# LED_Ring.net
KiCad netlist of a schematic drawn in Altium Designer
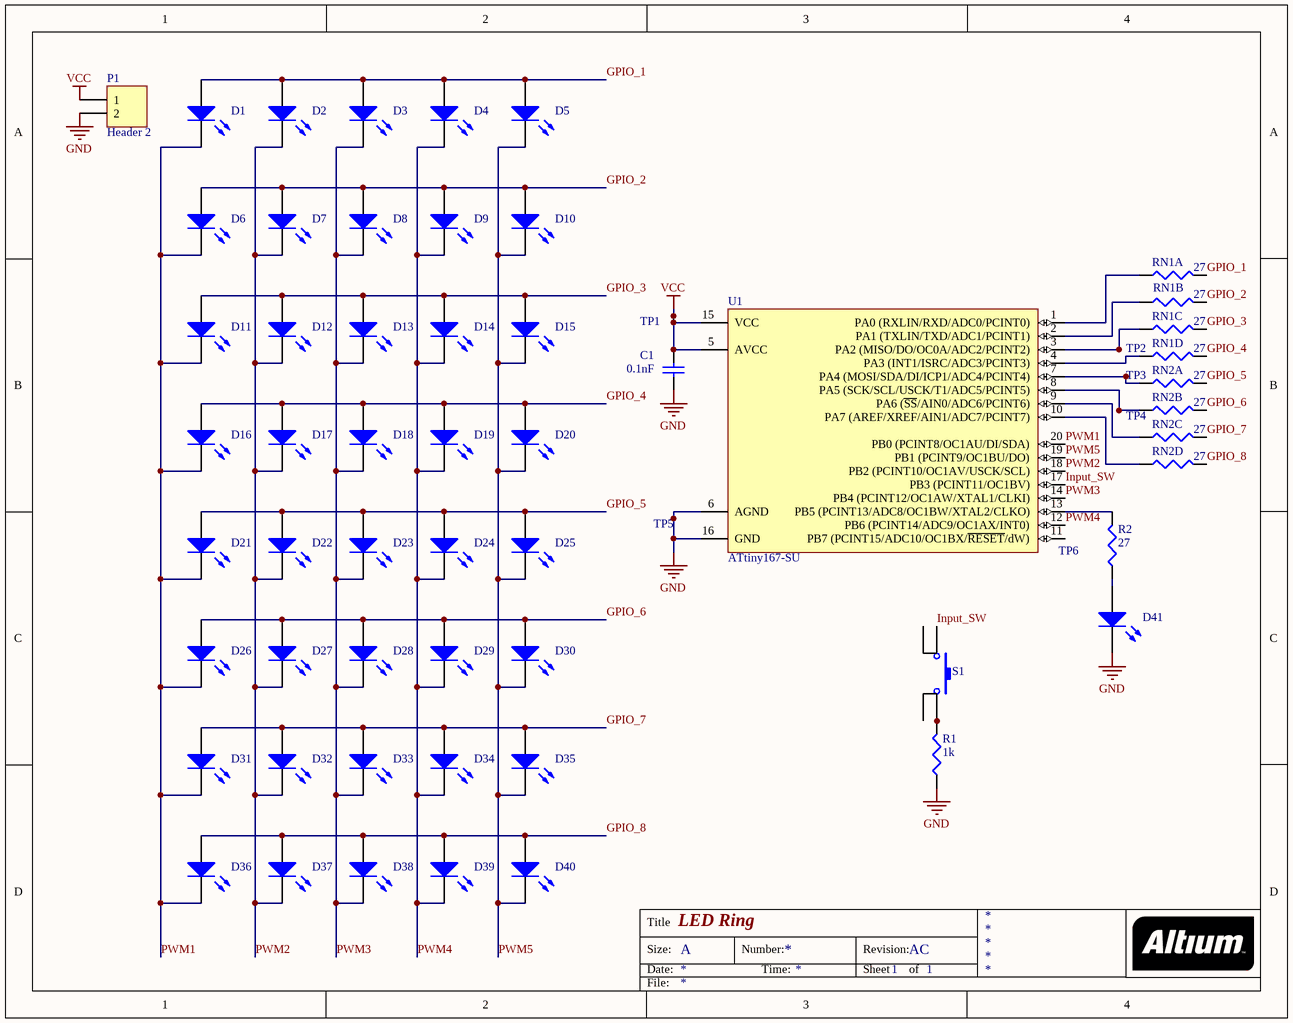
[diagram p0: LED_Ring.SchDoc]

(export (version "E")
  (design (tool "Eeschema 10.0.6"))
  (components
    (comp (ref "C1")
      (value "0.1nF")
      (footprint "1608[0603]")
      (description "Capacitor (Semiconductor SIM Model)")
      (fields (field (name "Comment") "Cap Semi") (field (name "PUBLISHER") "Altium Limited"))
      (libsource (lib "Miscellaneous Devices") (part "Cap Semi"))
    )
    (comp (ref "D1")
      (value "475-1410-1-ND")
      (footprint "0805")
      (description "OSRAM LG R971-KN-1, 0805, Green")
      (fields (field (name "PUBLISHER") "Altium Limited"))
      (libsource (lib "Digikey") (part "475-1410-1-ND"))
    )
    (comp (ref "D2")
      (value "475-1410-1-ND")
      (footprint "0805")
      (description "OSRAM LG R971-KN-1, 0805, Green")
      (fields (field (name "PUBLISHER") "Altium Limited"))
      (libsource (lib "Digikey") (part "475-1410-1-ND"))
    )
    (comp (ref "D3")
      (value "475-1410-1-ND")
      (footprint "0805")
      (description "OSRAM LG R971-KN-1, 0805, Green")
      (fields (field (name "PUBLISHER") "Altium Limited"))
      (libsource (lib "Digikey") (part "475-1410-1-ND"))
    )
    (comp (ref "D4")
      (value "475-1410-1-ND")
      (footprint "0805")
      (description "OSRAM LG R971-KN-1, 0805, Green")
      (fields (field (name "PUBLISHER") "Altium Limited"))
      (libsource (lib "Digikey") (part "475-1410-1-ND"))
    )
    (comp (ref "D5")
      (value "475-1410-1-ND")
      (footprint "0805")
      (description "OSRAM LG R971-KN-1, 0805, Green")
      (fields (field (name "PUBLISHER") "Altium Limited"))
      (libsource (lib "Digikey") (part "475-1410-1-ND"))
    )
    (comp (ref "D6")
      (value "475-1410-1-ND")
      (footprint "0805")
      (description "OSRAM LG R971-KN-1, 0805, Green")
      (fields (field (name "PUBLISHER") "Altium Limited"))
      (libsource (lib "Digikey") (part "475-1410-1-ND"))
    )
    (comp (ref "D7")
      (value "475-1410-1-ND")
      (footprint "0805")
      (description "OSRAM LG R971-KN-1, 0805, Green")
      (fields (field (name "PUBLISHER") "Altium Limited"))
      (libsource (lib "Digikey") (part "475-1410-1-ND"))
    )
    (comp (ref "D8")
      (value "475-1410-1-ND")
      (footprint "0805")
      (description "OSRAM LG R971-KN-1, 0805, Green")
      (fields (field (name "PUBLISHER") "Altium Limited"))
      (libsource (lib "Digikey") (part "475-1410-1-ND"))
    )
    (comp (ref "D9")
      (value "475-1410-1-ND")
      (footprint "0805")
      (description "OSRAM LG R971-KN-1, 0805, Green")
      (fields (field (name "PUBLISHER") "Altium Limited"))
      (libsource (lib "Digikey") (part "475-1410-1-ND"))
    )
    (comp (ref "D10")
      (value "475-1410-1-ND")
      (footprint "0805")
      (description "OSRAM LG R971-KN-1, 0805, Green")
      (fields (field (name "PUBLISHER") "Altium Limited"))
      (libsource (lib "Digikey") (part "475-1410-1-ND"))
    )
    (comp (ref "D11")
      (value "475-1410-1-ND")
      (footprint "0805")
      (description "OSRAM LG R971-KN-1, 0805, Green")
      (fields (field (name "PUBLISHER") "Altium Limited"))
      (libsource (lib "Digikey") (part "475-1410-1-ND"))
    )
    (comp (ref "D12")
      (value "475-1410-1-ND")
      (footprint "0805")
      (description "OSRAM LG R971-KN-1, 0805, Green")
      (fields (field (name "PUBLISHER") "Altium Limited"))
      (libsource (lib "Digikey") (part "475-1410-1-ND"))
    )
    (comp (ref "D13")
      (value "475-1410-1-ND")
      (footprint "0805")
      (description "OSRAM LG R971-KN-1, 0805, Green")
      (fields (field (name "PUBLISHER") "Altium Limited"))
      (libsource (lib "Digikey") (part "475-1410-1-ND"))
    )
    (comp (ref "D14")
      (value "475-1410-1-ND")
      (footprint "0805")
      (description "OSRAM LG R971-KN-1, 0805, Green")
      (fields (field (name "PUBLISHER") "Altium Limited"))
      (libsource (lib "Digikey") (part "475-1410-1-ND"))
    )
    (comp (ref "D15")
      (value "475-1410-1-ND")
      (footprint "0805")
      (description "OSRAM LG R971-KN-1, 0805, Green")
      (fields (field (name "PUBLISHER") "Altium Limited"))
      (libsource (lib "Digikey") (part "475-1410-1-ND"))
    )
    (comp (ref "D16")
      (value "475-1410-1-ND")
      (footprint "0805")
      (description "OSRAM LG R971-KN-1, 0805, Green")
      (fields (field (name "PUBLISHER") "Altium Limited"))
      (libsource (lib "Digikey") (part "475-1410-1-ND"))
    )
    (comp (ref "D17")
      (value "475-1410-1-ND")
      (footprint "0805")
      (description "OSRAM LG R971-KN-1, 0805, Green")
      (fields (field (name "PUBLISHER") "Altium Limited"))
      (libsource (lib "Digikey") (part "475-1410-1-ND"))
    )
    (comp (ref "D18")
      (value "475-1410-1-ND")
      (footprint "0805")
      (description "OSRAM LG R971-KN-1, 0805, Green")
      (fields (field (name "PUBLISHER") "Altium Limited"))
      (libsource (lib "Digikey") (part "475-1410-1-ND"))
    )
    (comp (ref "D19")
      (value "475-1410-1-ND")
      (footprint "0805")
      (description "OSRAM LG R971-KN-1, 0805, Green")
      (fields (field (name "PUBLISHER") "Altium Limited"))
      (libsource (lib "Digikey") (part "475-1410-1-ND"))
    )
    (comp (ref "D20")
      (value "475-1410-1-ND")
      (footprint "0805")
      (description "OSRAM LG R971-KN-1, 0805, Green")
      (fields (field (name "PUBLISHER") "Altium Limited"))
      (libsource (lib "Digikey") (part "475-1410-1-ND"))
    )
    (comp (ref "D21")
      (value "475-1410-1-ND")
      (footprint "0805")
      (description "OSRAM LG R971-KN-1, 0805, Green")
      (fields (field (name "PUBLISHER") "Altium Limited"))
      (libsource (lib "Digikey") (part "475-1410-1-ND"))
    )
    (comp (ref "D22")
      (value "475-1410-1-ND")
      (footprint "0805")
      (description "OSRAM LG R971-KN-1, 0805, Green")
      (fields (field (name "PUBLISHER") "Altium Limited"))
      (libsource (lib "Digikey") (part "475-1410-1-ND"))
    )
    (comp (ref "D23")
      (value "475-1410-1-ND")
      (footprint "0805")
      (description "OSRAM LG R971-KN-1, 0805, Green")
      (fields (field (name "PUBLISHER") "Altium Limited"))
      (libsource (lib "Digikey") (part "475-1410-1-ND"))
    )
    (comp (ref "D24")
      (value "475-1410-1-ND")
      (footprint "0805")
      (description "OSRAM LG R971-KN-1, 0805, Green")
      (fields (field (name "PUBLISHER") "Altium Limited"))
      (libsource (lib "Digikey") (part "475-1410-1-ND"))
    )
    (comp (ref "D25")
      (value "475-1410-1-ND")
      (footprint "0805")
      (description "OSRAM LG R971-KN-1, 0805, Green")
      (fields (field (name "PUBLISHER") "Altium Limited"))
      (libsource (lib "Digikey") (part "475-1410-1-ND"))
    )
    (comp (ref "D26")
      (value "475-1410-1-ND")
      (footprint "0805")
      (description "OSRAM LG R971-KN-1, 0805, Green")
      (fields (field (name "PUBLISHER") "Altium Limited"))
      (libsource (lib "Digikey") (part "475-1410-1-ND"))
    )
    (comp (ref "D27")
      (value "475-1410-1-ND")
      (footprint "0805")
      (description "OSRAM LG R971-KN-1, 0805, Green")
      (fields (field (name "PUBLISHER") "Altium Limited"))
      (libsource (lib "Digikey") (part "475-1410-1-ND"))
    )
    (comp (ref "D28")
      (value "475-1410-1-ND")
      (footprint "0805")
      (description "OSRAM LG R971-KN-1, 0805, Green")
      (fields (field (name "PUBLISHER") "Altium Limited"))
      (libsource (lib "Digikey") (part "475-1410-1-ND"))
    )
    (comp (ref "D29")
      (value "475-1410-1-ND")
      (footprint "0805")
      (description "OSRAM LG R971-KN-1, 0805, Green")
      (fields (field (name "PUBLISHER") "Altium Limited"))
      (libsource (lib "Digikey") (part "475-1410-1-ND"))
    )
    (comp (ref "D30")
      (value "475-1410-1-ND")
      (footprint "0805")
      (description "OSRAM LG R971-KN-1, 0805, Green")
      (fields (field (name "PUBLISHER") "Altium Limited"))
      (libsource (lib "Digikey") (part "475-1410-1-ND"))
    )
    (comp (ref "D31")
      (value "475-1410-1-ND")
      (footprint "0805")
      (description "OSRAM LG R971-KN-1, 0805, Green")
      (fields (field (name "PUBLISHER") "Altium Limited"))
      (libsource (lib "Digikey") (part "475-1410-1-ND"))
    )
    (comp (ref "D32")
      (value "475-1410-1-ND")
      (footprint "0805")
      (description "OSRAM LG R971-KN-1, 0805, Green")
      (fields (field (name "PUBLISHER") "Altium Limited"))
      (libsource (lib "Digikey") (part "475-1410-1-ND"))
    )
    (comp (ref "D33")
      (value "475-1410-1-ND")
      (footprint "0805")
      (description "OSRAM LG R971-KN-1, 0805, Green")
      (fields (field (name "PUBLISHER") "Altium Limited"))
      (libsource (lib "Digikey") (part "475-1410-1-ND"))
    )
    (comp (ref "D34")
      (value "475-1410-1-ND")
      (footprint "0805")
      (description "OSRAM LG R971-KN-1, 0805, Green")
      (fields (field (name "PUBLISHER") "Altium Limited"))
      (libsource (lib "Digikey") (part "475-1410-1-ND"))
    )
    (comp (ref "D35")
      (value "475-1410-1-ND")
      (footprint "0805")
      (description "OSRAM LG R971-KN-1, 0805, Green")
      (fields (field (name "PUBLISHER") "Altium Limited"))
      (libsource (lib "Digikey") (part "475-1410-1-ND"))
    )
    (comp (ref "D36")
      (value "475-1410-1-ND")
      (footprint "0805")
      (description "OSRAM LG R971-KN-1, 0805, Green")
      (fields (field (name "PUBLISHER") "Altium Limited"))
      (libsource (lib "Digikey") (part "475-1410-1-ND"))
    )
    (comp (ref "D37")
      (value "475-1410-1-ND")
      (footprint "0805")
      (description "OSRAM LG R971-KN-1, 0805, Green")
      (fields (field (name "PUBLISHER") "Altium Limited"))
      (libsource (lib "Digikey") (part "475-1410-1-ND"))
    )
    (comp (ref "D38")
      (value "475-1410-1-ND")
      (footprint "0805")
      (description "OSRAM LG R971-KN-1, 0805, Green")
      (fields (field (name "PUBLISHER") "Altium Limited"))
      (libsource (lib "Digikey") (part "475-1410-1-ND"))
    )
    (comp (ref "D39")
      (value "475-1410-1-ND")
      (footprint "0805")
      (description "OSRAM LG R971-KN-1, 0805, Green")
      (fields (field (name "PUBLISHER") "Altium Limited"))
      (libsource (lib "Digikey") (part "475-1410-1-ND"))
    )
    (comp (ref "D40")
      (value "475-1410-1-ND")
      (footprint "0805")
      (description "OSRAM LG R971-KN-1, 0805, Green")
      (fields (field (name "PUBLISHER") "Altium Limited"))
      (libsource (lib "Digikey") (part "475-1410-1-ND"))
    )
    (comp (ref "D41")
      (value "475-1410-1-ND")
      (footprint "0805")
      (description "OSRAM LG R971-KN-1, 0805, Green")
      (fields (field (name "PUBLISHER") "Altium Limited"))
      (libsource (lib "Digikey") (part "475-1410-1-ND"))
    )
    (comp (ref "P1")
      (value "Header 2")
      (footprint "HDR1X2")
      (description "Header, 2-Pin")
      (fields (field (name "PUBLISHER") "Altium Limited"))
      (libsource (lib "Miscellaneous Connectors") (part "Header 2"))
    )
    (comp (ref "R1")
      (value "1k")
      (footprint "RC0805")
      (description "RES SMD 1K OHM 1% 1/8W 0805")
      (fields
        (field (name "MANUFACTURER") "Yageo")
        (field (name "MANUFACTURER PART NUMBER") "RC0805FR-071KL")
      )
      (libsource (lib "Digikey") (part "RC0805FR-071KL"))
    )
    (comp (ref "R2")
      (value "27")
      (footprint "RC0805")
      (description "RES SMD 27 OHM 1% 1/8W 0805")
      (fields
        (field (name "MANUFACTURER") "Yageo")
        (field (name "MANUFACTURER PART NUMBER") "RC0805FR-0727RL")
      )
      (libsource (lib "Digikey") (part "RC0805FR-0727RL"))
    )
    (comp (ref "RN1")
      (value "27")
      (footprint "4x0603")
      (description "Resistor Network")
      (fields (field (name "Comment") "YC164J-27CT-ND") (field (name "PUBLISHER") "Bob Adams"))
      (libsource (lib "Digikey") (part "YC164J-27CT-ND"))
    )
    (comp (ref "RN2")
      (value "27")
      (footprint "4x0603")
      (description "Resistor Network")
      (fields (field (name "Comment") "YC164J-27CT-ND") (field (name "PUBLISHER") "Bob Adams"))
      (libsource (lib "Digikey") (part "YC164J-27CT-ND"))
    )
    (comp (ref "S1")
      (value "OFF-MOM switch, 10mA")
      (footprint "EG4793-ND")
      (description "EG4793-ND")
      (fields (field (name "PUBLISHER") "Altium Limited"))
      (libsource (lib "Digikey") (part "OFF-MOM switch, 10mA"))
    )
    (comp (ref "TP1") (value "TP") (footprint "TP") (libsource (lib "Digikey") (part "TP")))
    (comp (ref "TP2") (value "TP") (footprint "TP") (libsource (lib "Digikey") (part "TP")))
    (comp (ref "TP3") (value "TP") (footprint "TP") (libsource (lib "Digikey") (part "TP")))
    (comp (ref "TP4") (value "TP") (footprint "TP") (libsource (lib "Digikey") (part "TP")))
    (comp (ref "TP5") (value "TP") (footprint "TP") (libsource (lib "Digikey") (part "TP")))
    (comp (ref "TP6") (value "TP") (footprint "TP") (libsource (lib "Digikey") (part "TP")))
    (comp (ref "U1")
      (value "ATtiny167-SU")
      (footprint "20S2_N")
      (libsource (lib "Atmel Microcontroller tinyAVR") (part "ATtiny167-SU"))
    )
  )
  (nets
    (net (code "1") (name "/GPIO_1") (class "Default")
      (node (ref "D1") (pin "1") (pinfunction "A_1") (pintype "passive"))
      (node (ref "D2") (pin "1") (pinfunction "A_1") (pintype "passive"))
      (node (ref "D3") (pin "1") (pinfunction "A_1") (pintype "passive"))
      (node (ref "D4") (pin "1") (pinfunction "A_1") (pintype "passive"))
      (node (ref "D5") (pin "1") (pinfunction "A_1") (pintype "passive"))
      (node (ref "RN1") (pin "2") (pinfunction "2_2") (pintype "passive"))
    )
    (net (code "2") (name "/GPIO_2") (class "Default")
      (node (ref "D10") (pin "1") (pinfunction "A_1") (pintype "passive"))
      (node (ref "D6") (pin "1") (pinfunction "A_1") (pintype "passive"))
      (node (ref "D7") (pin "1") (pinfunction "A_1") (pintype "passive"))
      (node (ref "D8") (pin "1") (pinfunction "A_1") (pintype "passive"))
      (node (ref "D9") (pin "1") (pinfunction "A_1") (pintype "passive"))
      (node (ref "RN1") (pin "4") (pinfunction "4_4") (pintype "passive"))
    )
    (net (code "3") (name "/GPIO_3") (class "Default")
      (node (ref "D11") (pin "1") (pinfunction "A_1") (pintype "passive"))
      (node (ref "D12") (pin "1") (pinfunction "A_1") (pintype "passive"))
      (node (ref "D13") (pin "1") (pinfunction "A_1") (pintype "passive"))
      (node (ref "D14") (pin "1") (pinfunction "A_1") (pintype "passive"))
      (node (ref "D15") (pin "1") (pinfunction "A_1") (pintype "passive"))
      (node (ref "RN1") (pin "6") (pinfunction "6_6") (pintype "passive"))
    )
    (net (code "4") (name "/GPIO_4") (class "Default")
      (node (ref "D16") (pin "1") (pinfunction "A_1") (pintype "passive"))
      (node (ref "D17") (pin "1") (pinfunction "A_1") (pintype "passive"))
      (node (ref "D18") (pin "1") (pinfunction "A_1") (pintype "passive"))
      (node (ref "D19") (pin "1") (pinfunction "A_1") (pintype "passive"))
      (node (ref "D20") (pin "1") (pinfunction "A_1") (pintype "passive"))
      (node (ref "RN1") (pin "8") (pinfunction "8_8") (pintype "passive"))
    )
    (net (code "5") (name "/GPIO_5") (class "Default")
      (node (ref "D21") (pin "1") (pinfunction "A_1") (pintype "passive"))
      (node (ref "D22") (pin "1") (pinfunction "A_1") (pintype "passive"))
      (node (ref "D23") (pin "1") (pinfunction "A_1") (pintype "passive"))
      (node (ref "D24") (pin "1") (pinfunction "A_1") (pintype "passive"))
      (node (ref "D25") (pin "1") (pinfunction "A_1") (pintype "passive"))
      (node (ref "RN2") (pin "2") (pinfunction "2_2") (pintype "passive"))
    )
    (net (code "6") (name "/GPIO_6") (class "Default")
      (node (ref "D26") (pin "1") (pinfunction "A_1") (pintype "passive"))
      (node (ref "D27") (pin "1") (pinfunction "A_1") (pintype "passive"))
      (node (ref "D28") (pin "1") (pinfunction "A_1") (pintype "passive"))
      (node (ref "D29") (pin "1") (pinfunction "A_1") (pintype "passive"))
      (node (ref "D30") (pin "1") (pinfunction "A_1") (pintype "passive"))
      (node (ref "RN2") (pin "4") (pinfunction "4_4") (pintype "passive"))
    )
    (net (code "7") (name "/GPIO_7") (class "Default")
      (node (ref "D31") (pin "1") (pinfunction "A_1") (pintype "passive"))
      (node (ref "D32") (pin "1") (pinfunction "A_1") (pintype "passive"))
      (node (ref "D33") (pin "1") (pinfunction "A_1") (pintype "passive"))
      (node (ref "D34") (pin "1") (pinfunction "A_1") (pintype "passive"))
      (node (ref "D35") (pin "1") (pinfunction "A_1") (pintype "passive"))
      (node (ref "RN2") (pin "6") (pinfunction "6_6") (pintype "passive"))
    )
    (net (code "8") (name "/GPIO_8") (class "Default")
      (node (ref "D36") (pin "1") (pinfunction "A_1") (pintype "passive"))
      (node (ref "D37") (pin "1") (pinfunction "A_1") (pintype "passive"))
      (node (ref "D38") (pin "1") (pinfunction "A_1") (pintype "passive"))
      (node (ref "D39") (pin "1") (pinfunction "A_1") (pintype "passive"))
      (node (ref "D40") (pin "1") (pinfunction "A_1") (pintype "passive"))
      (node (ref "RN2") (pin "8") (pinfunction "8_8") (pintype "passive"))
    )
    (net (code "9") (name "/Input_SW") (class "Default")
      (node (ref "S1") (pin "1") (pinfunction "1_1") (pintype "passive"))
      (node (ref "U1") (pin "17") (pinfunction "PB3_(PCINT11/OC1BV)_17") (pintype "bidirectional"))
    )
    (net (code "10") (name "/PWM1") (class "Default")
      (node (ref "D1") (pin "2") (pinfunction "K_2") (pintype "passive"))
      (node (ref "D11") (pin "2") (pinfunction "K_2") (pintype "passive"))
      (node (ref "D16") (pin "2") (pinfunction "K_2") (pintype "passive"))
      (node (ref "D21") (pin "2") (pinfunction "K_2") (pintype "passive"))
      (node (ref "D26") (pin "2") (pinfunction "K_2") (pintype "passive"))
      (node (ref "D31") (pin "2") (pinfunction "K_2") (pintype "passive"))
      (node (ref "D36") (pin "2") (pinfunction "K_2") (pintype "passive"))
      (node (ref "D6") (pin "2") (pinfunction "K_2") (pintype "passive"))
      (node (ref "U1") (pin "20") (pinfunction "PB0_(PCINT8/OC1AU/DI/SDA)_20") (pintype "bidirectional"))
    )
    (net (code "11") (name "/PWM2") (class "Default")
      (node (ref "D12") (pin "2") (pinfunction "K_2") (pintype "passive"))
      (node (ref "D17") (pin "2") (pinfunction "K_2") (pintype "passive"))
      (node (ref "D2") (pin "2") (pinfunction "K_2") (pintype "passive"))
      (node (ref "D22") (pin "2") (pinfunction "K_2") (pintype "passive"))
      (node (ref "D27") (pin "2") (pinfunction "K_2") (pintype "passive"))
      (node (ref "D32") (pin "2") (pinfunction "K_2") (pintype "passive"))
      (node (ref "D37") (pin "2") (pinfunction "K_2") (pintype "passive"))
      (node (ref "D7") (pin "2") (pinfunction "K_2") (pintype "passive"))
      (node (ref "U1") (pin "18") (pinfunction "PB2_(PCINT10/OC1AV/USCK/SCL)_18") (pintype "bidirectional"))
    )
    (net (code "12") (name "/PWM3") (class "Default")
      (node (ref "D13") (pin "2") (pinfunction "K_2") (pintype "passive"))
      (node (ref "D18") (pin "2") (pinfunction "K_2") (pintype "passive"))
      (node (ref "D23") (pin "2") (pinfunction "K_2") (pintype "passive"))
      (node (ref "D28") (pin "2") (pinfunction "K_2") (pintype "passive"))
      (node (ref "D3") (pin "2") (pinfunction "K_2") (pintype "passive"))
      (node (ref "D33") (pin "2") (pinfunction "K_2") (pintype "passive"))
      (node (ref "D38") (pin "2") (pinfunction "K_2") (pintype "passive"))
      (node (ref "D8") (pin "2") (pinfunction "K_2") (pintype "passive"))
      (node (ref "U1") (pin "14") (pinfunction "PB4_(PCINT12/OC1AW/XTAL1/CLKI)_14") (pintype "bidirectional"))
    )
    (net (code "13") (name "/PWM4") (class "Default")
      (node (ref "D14") (pin "2") (pinfunction "K_2") (pintype "passive"))
      (node (ref "D19") (pin "2") (pinfunction "K_2") (pintype "passive"))
      (node (ref "D24") (pin "2") (pinfunction "K_2") (pintype "passive"))
      (node (ref "D29") (pin "2") (pinfunction "K_2") (pintype "passive"))
      (node (ref "D34") (pin "2") (pinfunction "K_2") (pintype "passive"))
      (node (ref "D39") (pin "2") (pinfunction "K_2") (pintype "passive"))
      (node (ref "D4") (pin "2") (pinfunction "K_2") (pintype "passive"))
      (node (ref "D9") (pin "2") (pinfunction "K_2") (pintype "passive"))
      (node (ref "U1") (pin "12") (pinfunction "PB6_(PCINT14/ADC9/OC1AX/INT0)_12") (pintype "bidirectional"))
    )
    (net (code "14") (name "/PWM5") (class "Default")
      (node (ref "D10") (pin "2") (pinfunction "K_2") (pintype "passive"))
      (node (ref "D15") (pin "2") (pinfunction "K_2") (pintype "passive"))
      (node (ref "D20") (pin "2") (pinfunction "K_2") (pintype "passive"))
      (node (ref "D25") (pin "2") (pinfunction "K_2") (pintype "passive"))
      (node (ref "D30") (pin "2") (pinfunction "K_2") (pintype "passive"))
      (node (ref "D35") (pin "2") (pinfunction "K_2") (pintype "passive"))
      (node (ref "D40") (pin "2") (pinfunction "K_2") (pintype "passive"))
      (node (ref "D5") (pin "2") (pinfunction "K_2") (pintype "passive"))
      (node (ref "U1") (pin "19") (pinfunction "PB1_(PCINT9/OC1BU/DO)_19") (pintype "bidirectional"))
    )
    (net (code "15") (name "GND") (class "Default")
      (node (ref "C1") (pin "1") (pinfunction "1_1") (pintype "passive"))
      (node (ref "D41") (pin "2") (pinfunction "K_2") (pintype "passive"))
      (node (ref "P1") (pin "2") (pinfunction "2_2") (pintype "passive"))
      (node (ref "R1") (pin "1") (pinfunction "1_1") (pintype "passive"))
      (node (ref "TP5") (pin "1") (pinfunction "1_1") (pintype "passive"))
      (node (ref "U1") (pin "16") (pinfunction "GND_16") (pintype "power_in"))
      (node (ref "U1") (pin "6") (pinfunction "AGND_6") (pintype "power_in"))
    )
    (net (code "16") (name "Net-(D41-A)") (class "Default")
      (node (ref "D41") (pin "1") (pinfunction "A_1") (pintype "passive"))
      (node (ref "R2") (pin "1") (pinfunction "1_1") (pintype "passive"))
    )
    (net (code "17") (name "Net-(R1-Pad2)") (class "Default")
      (node (ref "R1") (pin "2") (pinfunction "2_2") (pintype "passive"))
      (node (ref "S1") (pin "2") (pinfunction "2_2") (pintype "passive"))
    )
    (net (code "18") (name "Net-(U1-PA0_(RXLIN{slash}RXD{slash}ADC0{slash}PCINT0))") (class "Default")
      (node (ref "RN1") (pin "1") (pinfunction "1_1") (pintype "passive"))
      (node (ref "U1") (pin "1") (pinfunction "PA0_(RXLIN/RXD/ADC0/PCINT0)_1") (pintype "bidirectional"))
    )
    (net (code "19") (name "Net-(U1-PA1_(TXLIN{slash}TXD{slash}ADC1{slash}PCINT1))") (class "Default")
      (node (ref "RN1") (pin "3") (pinfunction "3_3") (pintype "passive"))
      (node (ref "U1") (pin "2") (pinfunction "PA1_(TXLIN/TXD/ADC1/PCINT1)_2") (pintype "bidirectional"))
    )
    (net (code "20") (name "Net-(U1-PA2_(MISO{slash}DO{slash}OC0A{slash}ADC2{slash}PCINT2))") (class "Default")
      (node (ref "RN1") (pin "5") (pinfunction "5_5") (pintype "passive"))
      (node (ref "TP2") (pin "1") (pinfunction "1_1") (pintype "passive"))
      (node (ref "U1") (pin "3") (pinfunction "PA2_(MISO/DO/OC0A/ADC2/PCINT2)_3") (pintype "bidirectional"))
    )
    (net (code "21") (name "Net-(U1-PA3_(INT1{slash}ISRC{slash}ADC3{slash}PCINT3))") (class "Default")
      (node (ref "RN1") (pin "7") (pinfunction "7_7") (pintype "passive"))
      (node (ref "U1") (pin "4") (pinfunction "PA3_(INT1/ISRC/ADC3/PCINT3)_4") (pintype "bidirectional"))
    )
    (net (code "22") (name "Net-(U1-PA4_(MOSI{slash}SDA{slash}DI{slash}ICP1{slash}ADC4{slash}PCINT4))") (class "Default")
      (node (ref "RN2") (pin "1") (pinfunction "1_1") (pintype "passive"))
      (node (ref "TP3") (pin "1") (pinfunction "1_1") (pintype "passive"))
      (node (ref "U1") (pin "7") (pinfunction "PA4_(MOSI/SDA/DI/ICP1/ADC4/PCINT4)_7") (pintype "bidirectional"))
    )
    (net (code "23") (name "Net-(U1-PA5_(SCK{slash}SCL{slash}USCK{slash}T1{slash}ADC5{slash}PCINT5))") (class "Default")
      (node (ref "RN2") (pin "3") (pinfunction "3_3") (pintype "passive"))
      (node (ref "TP4") (pin "1") (pinfunction "1_1") (pintype "passive"))
      (node (ref "U1") (pin "8") (pinfunction "PA5_(SCK/SCL/USCK/T1/ADC5/PCINT5)_8") (pintype "bidirectional"))
    )
    (net (code "24") (name "Net-(U1-PA6_(~{SS}{slash}AIN0{slash}ADC6{slash}PCINT6))") (class "Default")
      (node (ref "RN2") (pin "5") (pinfunction "5_5") (pintype "passive"))
      (node (ref "U1") (pin "9") (pinfunction "PA6_(~{SS}/AIN0/ADC6/PCINT6)_9") (pintype "bidirectional"))
    )
    (net (code "25") (name "Net-(U1-PA7_(AREF{slash}XREF{slash}AIN1{slash}ADC7{slash}PCINT7))") (class "Default")
      (node (ref "RN2") (pin "7") (pinfunction "7_7") (pintype "passive"))
      (node (ref "U1") (pin "10") (pinfunction "PA7_(AREF/XREF/AIN1/ADC7/PCINT7)_10") (pintype "bidirectional"))
    )
    (net (code "26") (name "Net-(U1-PB5_(PCINT13{slash}ADC8{slash}OC1BW{slash}XTAL2{slash}CLKO))") (class "Default")
      (node (ref "R2") (pin "2") (pinfunction "2_2") (pintype "passive"))
      (node (ref "U1") (pin "13") (pinfunction "PB5_(PCINT13/ADC8/OC1BW/XTAL2/CLKO)_13") (pintype "bidirectional"))
    )
    (net (code "27") (name "Net-(U1-PB7_(PCINT15{slash}ADC10{slash}OC1BX{slash}~{RESET}{slash}dW))") (class "Default")
      (node (ref "TP6") (pin "1") (pinfunction "1_1") (pintype "passive"))
      (node (ref "U1") (pin "11") (pinfunction "PB7_(PCINT15/ADC10/OC1BX/~{RESET}/dW)_11") (pintype "bidirectional"))
    )
    (net (code "28") (name "VCC") (class "Default")
      (node (ref "C1") (pin "2") (pinfunction "2_2") (pintype "passive"))
      (node (ref "P1") (pin "1") (pinfunction "1_1") (pintype "passive"))
      (node (ref "TP1") (pin "1") (pinfunction "1_1") (pintype "passive"))
      (node (ref "U1") (pin "15") (pinfunction "VCC_15") (pintype "power_in"))
      (node (ref "U1") (pin "5") (pinfunction "AVCC_5") (pintype "power_in"))
    )
    (net (code "29") (name "unconnected-(S1-Pad3)") (class "Default")
      (node (ref "S1") (pin "3") (pinfunction "3_3") (pintype "passive"))
    )
    (net (code "30") (name "unconnected-(S1-Pad4)") (class "Default")
      (node (ref "S1") (pin "4") (pinfunction "4_4") (pintype "passive"))
    )
  )
)
